# SERVOS-1.net
KiCad netlist of a schematic drawn in EAGLE
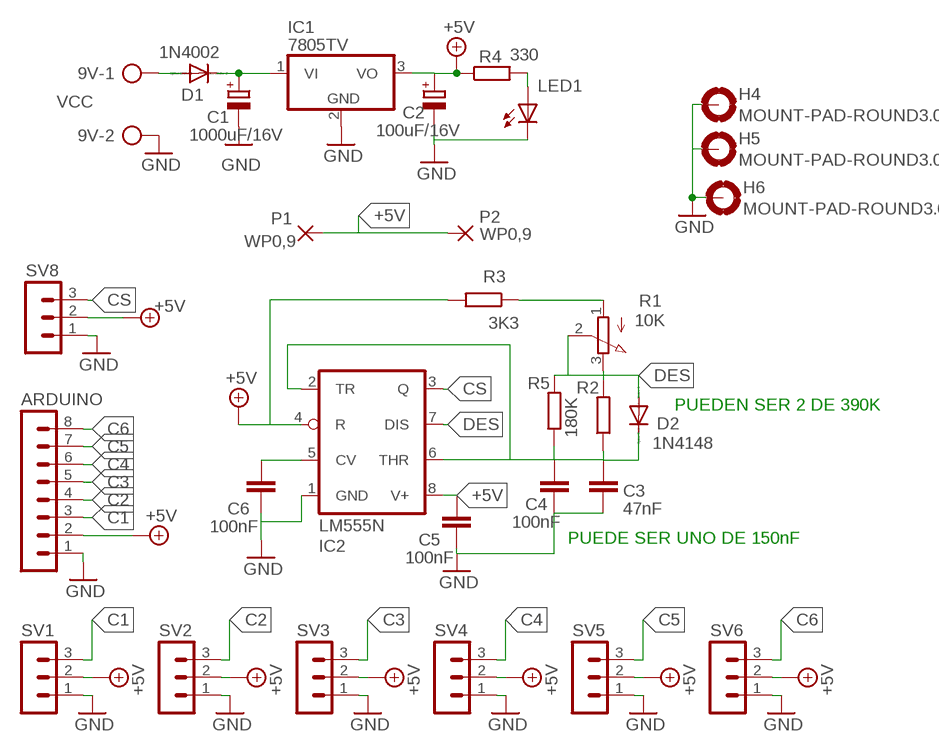
[diagram p0: schematic, sheet 1]

(export (version "E")
  (design (tool "Eeschema 10.0.6"))
  (components
    (comp (ref "9V")
      (value "VCC")
      (footprint "eagle-import:AK500_2")
      (libsource (lib "eagle-import") (part "AK500/2"))
    )
    (comp (ref "ARDUINO")
      (value "MA08-1")
      (footprint "eagle-import:MA08-1")
      (libsource (lib "eagle-import") (part "MA08-1"))
    )
    (comp (ref "C1")
      (value "1000uF/16V")
      (footprint "eagle-import:E2,5-7")
      (libsource (lib "eagle-import") (part "CPOL-EUE2.5-7"))
    )
    (comp (ref "C2")
      (value "100uF/16V")
      (footprint "eagle-import:E2,5-5")
      (libsource (lib "eagle-import") (part "CPOL-EUE2.5-5"))
    )
    (comp (ref "C3")
      (value "47nF")
      (footprint "eagle-import:C025_050-025X075")
      (libsource (lib "eagle-import") (part "C-EU025_050-025X075"))
    )
    (comp (ref "C4")
      (value "100nF")
      (footprint "eagle-import:C025_050-025X075")
      (libsource (lib "eagle-import") (part "C-EU025_050-025X075"))
    )
    (comp (ref "C5")
      (value "100nF")
      (footprint "eagle-import:C025_050-025X075")
      (libsource (lib "eagle-import") (part "C-EU025_050-025X075"))
    )
    (comp (ref "C6")
      (value "100nF")
      (footprint "eagle-import:C025_050-025X075")
      (libsource (lib "eagle-import") (part "C-EU025_050-025X075"))
    )
    (comp (ref "D1")
      (value "1N4002")
      (footprint "eagle-import:DO35-7")
      (libsource (lib "eagle-import") (part "1N4148DO35-7"))
    )
    (comp (ref "D2")
      (value "1N4148")
      (footprint "eagle-import:DO35-7")
      (libsource (lib "eagle-import") (part "1N4148DO35-7"))
    )
    (comp (ref "H4")
      (value "MOUNT-PAD-ROUND3.0")
      (footprint "eagle-import:3,0-PAD")
      (libsource (lib "eagle-import") (part "MOUNT-PAD-ROUND3.0"))
    )
    (comp (ref "H5")
      (value "MOUNT-PAD-ROUND3.0")
      (footprint "eagle-import:3,0-PAD")
      (libsource (lib "eagle-import") (part "MOUNT-PAD-ROUND3.0"))
    )
    (comp (ref "H6")
      (value "MOUNT-PAD-ROUND3.0")
      (footprint "eagle-import:3,0-PAD")
      (libsource (lib "eagle-import") (part "MOUNT-PAD-ROUND3.0"))
    )
    (comp (ref "IC1")
      (value "7805TV")
      (footprint "eagle-import:TO220V")
      (libsource (lib "eagle-import") (part "78TV05"))
    )
    (comp (ref "IC2")
      (value "LM555N")
      (footprint "eagle-import:DIL08")
      (libsource (lib "eagle-import") (part "555NLM"))
    )
    (comp (ref "LED1")
      (value "LED3MM")
      (footprint "eagle-import:LED3MM")
      (libsource (lib "eagle-import") (part "LED3MM"))
    )
    (comp (ref "P1")
      (value "WP0,9")
      (footprint "eagle-import:1,6_0,9")
      (libsource (lib "eagle-import") (part "WIREPAD1,6/0,9"))
    )
    (comp (ref "P2")
      (value "WP0,9")
      (footprint "eagle-import:1,6_0,9")
      (libsource (lib "eagle-import") (part "WIREPAD1,6/0,9"))
    )
    (comp (ref "R1")
      (value "10K")
      (footprint "eagle-import:3RP_1610N")
      (libsource (lib "eagle-import") (part "3RP/1610N"))
    )
    (comp (ref "R2")
      (value "R-EU_0207/10")
      (footprint "eagle-import:0207_10")
      (libsource (lib "eagle-import") (part "R-EU_0207/10"))
    )
    (comp (ref "R3")
      (value "3K3")
      (footprint "eagle-import:0207_10")
      (libsource (lib "eagle-import") (part "R-EU_0207/10"))
    )
    (comp (ref "R4")
      (value "330")
      (footprint "eagle-import:0207_10")
      (libsource (lib "eagle-import") (part "R-EU_0207/10"))
    )
    (comp (ref "R5")
      (value "180K")
      (footprint "eagle-import:0207_10")
      (libsource (lib "eagle-import") (part "R-EU_0207/10"))
    )
    (comp (ref "SV1")
      (value "MA03-1")
      (footprint "eagle-import:MA03-1")
      (libsource (lib "eagle-import") (part "MA03-1"))
    )
    (comp (ref "SV2")
      (value "MA03-1")
      (footprint "eagle-import:MA03-1")
      (libsource (lib "eagle-import") (part "MA03-1"))
    )
    (comp (ref "SV3")
      (value "MA03-1")
      (footprint "eagle-import:MA03-1")
      (libsource (lib "eagle-import") (part "MA03-1"))
    )
    (comp (ref "SV4")
      (value "MA03-1")
      (footprint "eagle-import:MA03-1")
      (libsource (lib "eagle-import") (part "MA03-1"))
    )
    (comp (ref "SV5")
      (value "MA03-1")
      (footprint "eagle-import:MA03-1")
      (libsource (lib "eagle-import") (part "MA03-1"))
    )
    (comp (ref "SV6")
      (value "MA03-1")
      (footprint "eagle-import:MA03-1")
      (libsource (lib "eagle-import") (part "MA03-1"))
    )
    (comp (ref "SV8")
      (value "MA03-1")
      (footprint "eagle-import:MA03-1")
      (libsource (lib "eagle-import") (part "MA03-1"))
    )
  )
  (nets
    (net (code "1") (name "+5V") (class "Default")
      (node (ref "ARDUINO") (pin "2") (pinfunction "2_2") (pintype "passive"))
      (node (ref "C2") (pin "+") (pinfunction "+_+") (pintype "passive"))
      (node (ref "C5") (pin "1") (pinfunction "1_1") (pintype "passive"))
      (node (ref "IC1") (pin "3") (pinfunction "VO_3") (pintype "passive"))
      (node (ref "IC2") (pin "4") (pinfunction "R_4") (pintype "input"))
      (node (ref "IC2") (pin "8") (pinfunction "V+_8") (pintype "power_in"))
      (node (ref "P1") (pin "1") (pinfunction "P_1") (pintype "passive"))
      (node (ref "P2") (pin "1") (pinfunction "P_1") (pintype "passive"))
      (node (ref "R3") (pin "2") (pinfunction "2_2") (pintype "passive"))
      (node (ref "R4") (pin "1") (pinfunction "1_1") (pintype "passive"))
      (node (ref "SV1") (pin "2") (pinfunction "2_2") (pintype "passive"))
      (node (ref "SV2") (pin "2") (pinfunction "2_2") (pintype "passive"))
      (node (ref "SV3") (pin "2") (pinfunction "2_2") (pintype "passive"))
      (node (ref "SV4") (pin "2") (pinfunction "2_2") (pintype "passive"))
      (node (ref "SV5") (pin "2") (pinfunction "2_2") (pintype "passive"))
      (node (ref "SV6") (pin "2") (pinfunction "2_2") (pintype "passive"))
      (node (ref "SV8") (pin "2") (pinfunction "2_2") (pintype "passive"))
    )
    (net (code "2") (name "C1") (class "Default")
      (node (ref "ARDUINO") (pin "3") (pinfunction "3_3") (pintype "passive"))
      (node (ref "SV1") (pin "3") (pinfunction "3_3") (pintype "passive"))
    )
    (net (code "3") (name "C2") (class "Default")
      (node (ref "ARDUINO") (pin "4") (pinfunction "4_4") (pintype "passive"))
      (node (ref "SV2") (pin "3") (pinfunction "3_3") (pintype "passive"))
    )
    (net (code "4") (name "C3") (class "Default")
      (node (ref "ARDUINO") (pin "5") (pinfunction "5_5") (pintype "passive"))
      (node (ref "SV3") (pin "3") (pinfunction "3_3") (pintype "passive"))
    )
    (net (code "5") (name "C4") (class "Default")
      (node (ref "ARDUINO") (pin "6") (pinfunction "6_6") (pintype "passive"))
      (node (ref "SV4") (pin "3") (pinfunction "3_3") (pintype "passive"))
    )
    (net (code "6") (name "C5") (class "Default")
      (node (ref "ARDUINO") (pin "7") (pinfunction "7_7") (pintype "passive"))
      (node (ref "SV5") (pin "3") (pinfunction "3_3") (pintype "passive"))
    )
    (net (code "7") (name "C6") (class "Default")
      (node (ref "ARDUINO") (pin "8") (pinfunction "8_8") (pintype "passive"))
      (node (ref "SV6") (pin "3") (pinfunction "3_3") (pintype "passive"))
    )
    (net (code "8") (name "CS") (class "Default")
      (node (ref "IC2") (pin "3") (pinfunction "Q_3") (pintype "output"))
      (node (ref "SV8") (pin "3") (pinfunction "3_3") (pintype "passive"))
    )
    (net (code "9") (name "DES") (class "Default")
      (node (ref "D2") (pin "A") (pinfunction "A_A") (pintype "passive"))
      (node (ref "IC2") (pin "7") (pinfunction "DIS_7") (pintype "input"))
      (node (ref "R1") (pin "2") (pinfunction "S_2") (pintype "passive"))
      (node (ref "R1") (pin "3") (pinfunction "E_3") (pintype "passive"))
      (node (ref "R2") (pin "2") (pinfunction "2_2") (pintype "passive"))
      (node (ref "R5") (pin "2") (pinfunction "2_2") (pintype "passive"))
    )
    (net (code "10") (name "GND") (class "Default")
      (node (ref "9V") (pin "2") (pinfunction "KL_2") (pintype "passive"))
      (node (ref "ARDUINO") (pin "1") (pinfunction "1_1") (pintype "passive"))
      (node (ref "C1") (pin "-") (pinfunction "-_-") (pintype "passive"))
      (node (ref "C2") (pin "-") (pinfunction "-_-") (pintype "passive"))
      (node (ref "C3") (pin "2") (pinfunction "2_2") (pintype "passive"))
      (node (ref "C4") (pin "2") (pinfunction "2_2") (pintype "passive"))
      (node (ref "C5") (pin "2") (pinfunction "2_2") (pintype "passive"))
      (node (ref "C6") (pin "2") (pinfunction "2_2") (pintype "passive"))
      (node (ref "H4") (pin "B3,0") (pinfunction "MOUNT_B3,0") (pintype "passive"))
      (node (ref "H5") (pin "B3,0") (pinfunction "MOUNT_B3,0") (pintype "passive"))
      (node (ref "H6") (pin "B3,0") (pinfunction "MOUNT_B3,0") (pintype "passive"))
      (node (ref "IC1") (pin "2") (pinfunction "GND_2") (pintype "passive"))
      (node (ref "IC2") (pin "1") (pinfunction "GND_1") (pintype "power_in"))
      (node (ref "LED1") (pin "K") (pinfunction "C_K") (pintype "passive"))
      (node (ref "SV1") (pin "1") (pinfunction "1_1") (pintype "passive"))
      (node (ref "SV2") (pin "1") (pinfunction "1_1") (pintype "passive"))
      (node (ref "SV3") (pin "1") (pinfunction "1_1") (pintype "passive"))
      (node (ref "SV4") (pin "1") (pinfunction "1_1") (pintype "passive"))
      (node (ref "SV5") (pin "1") (pinfunction "1_1") (pintype "passive"))
      (node (ref "SV6") (pin "1") (pinfunction "1_1") (pintype "passive"))
      (node (ref "SV8") (pin "1") (pinfunction "1_1") (pintype "passive"))
    )
    (net (code "11") (name "Net-(9VA-KL)") (class "Default")
      (node (ref "9V") (pin "1") (pinfunction "KL_1") (pintype "passive"))
      (node (ref "D1") (pin "A") (pinfunction "A_A") (pintype "passive"))
    )
    (net (code "12") (name "Net-(IC1-VI)") (class "Default")
      (node (ref "C1") (pin "+") (pinfunction "+_+") (pintype "passive"))
      (node (ref "D1") (pin "C") (pinfunction "C_C") (pintype "passive"))
      (node (ref "IC1") (pin "1") (pinfunction "VI_1") (pintype "input"))
    )
    (net (code "13") (name "Net-(IC2-CV)") (class "Default")
      (node (ref "C6") (pin "1") (pinfunction "1_1") (pintype "passive"))
      (node (ref "IC2") (pin "5") (pinfunction "CV_5") (pintype "input"))
    )
    (net (code "14") (name "Net-(IC2-THR)") (class "Default")
      (node (ref "C3") (pin "1") (pinfunction "1_1") (pintype "passive"))
      (node (ref "C4") (pin "1") (pinfunction "1_1") (pintype "passive"))
      (node (ref "D2") (pin "C") (pinfunction "C_C") (pintype "passive"))
      (node (ref "IC2") (pin "2") (pinfunction "TR_2") (pintype "input"))
      (node (ref "IC2") (pin "6") (pinfunction "THR_6") (pintype "input"))
      (node (ref "R2") (pin "1") (pinfunction "1_1") (pintype "passive"))
      (node (ref "R5") (pin "1") (pinfunction "1_1") (pintype "passive"))
    )
    (net (code "15") (name "Net-(LED1-PadA)") (class "Default")
      (node (ref "LED1") (pin "A") (pinfunction "A_A") (pintype "passive"))
      (node (ref "R4") (pin "2") (pinfunction "2_2") (pintype "passive"))
    )
    (net (code "16") (name "Net-(R1-A)") (class "Default")
      (node (ref "R1") (pin "1") (pinfunction "A_1") (pintype "passive"))
      (node (ref "R3") (pin "1") (pinfunction "1_1") (pintype "passive"))
    )
  )
)
